# reader-and-latch-client-schematic.net
KiCad netlist of a schematic drawn in EAGLE
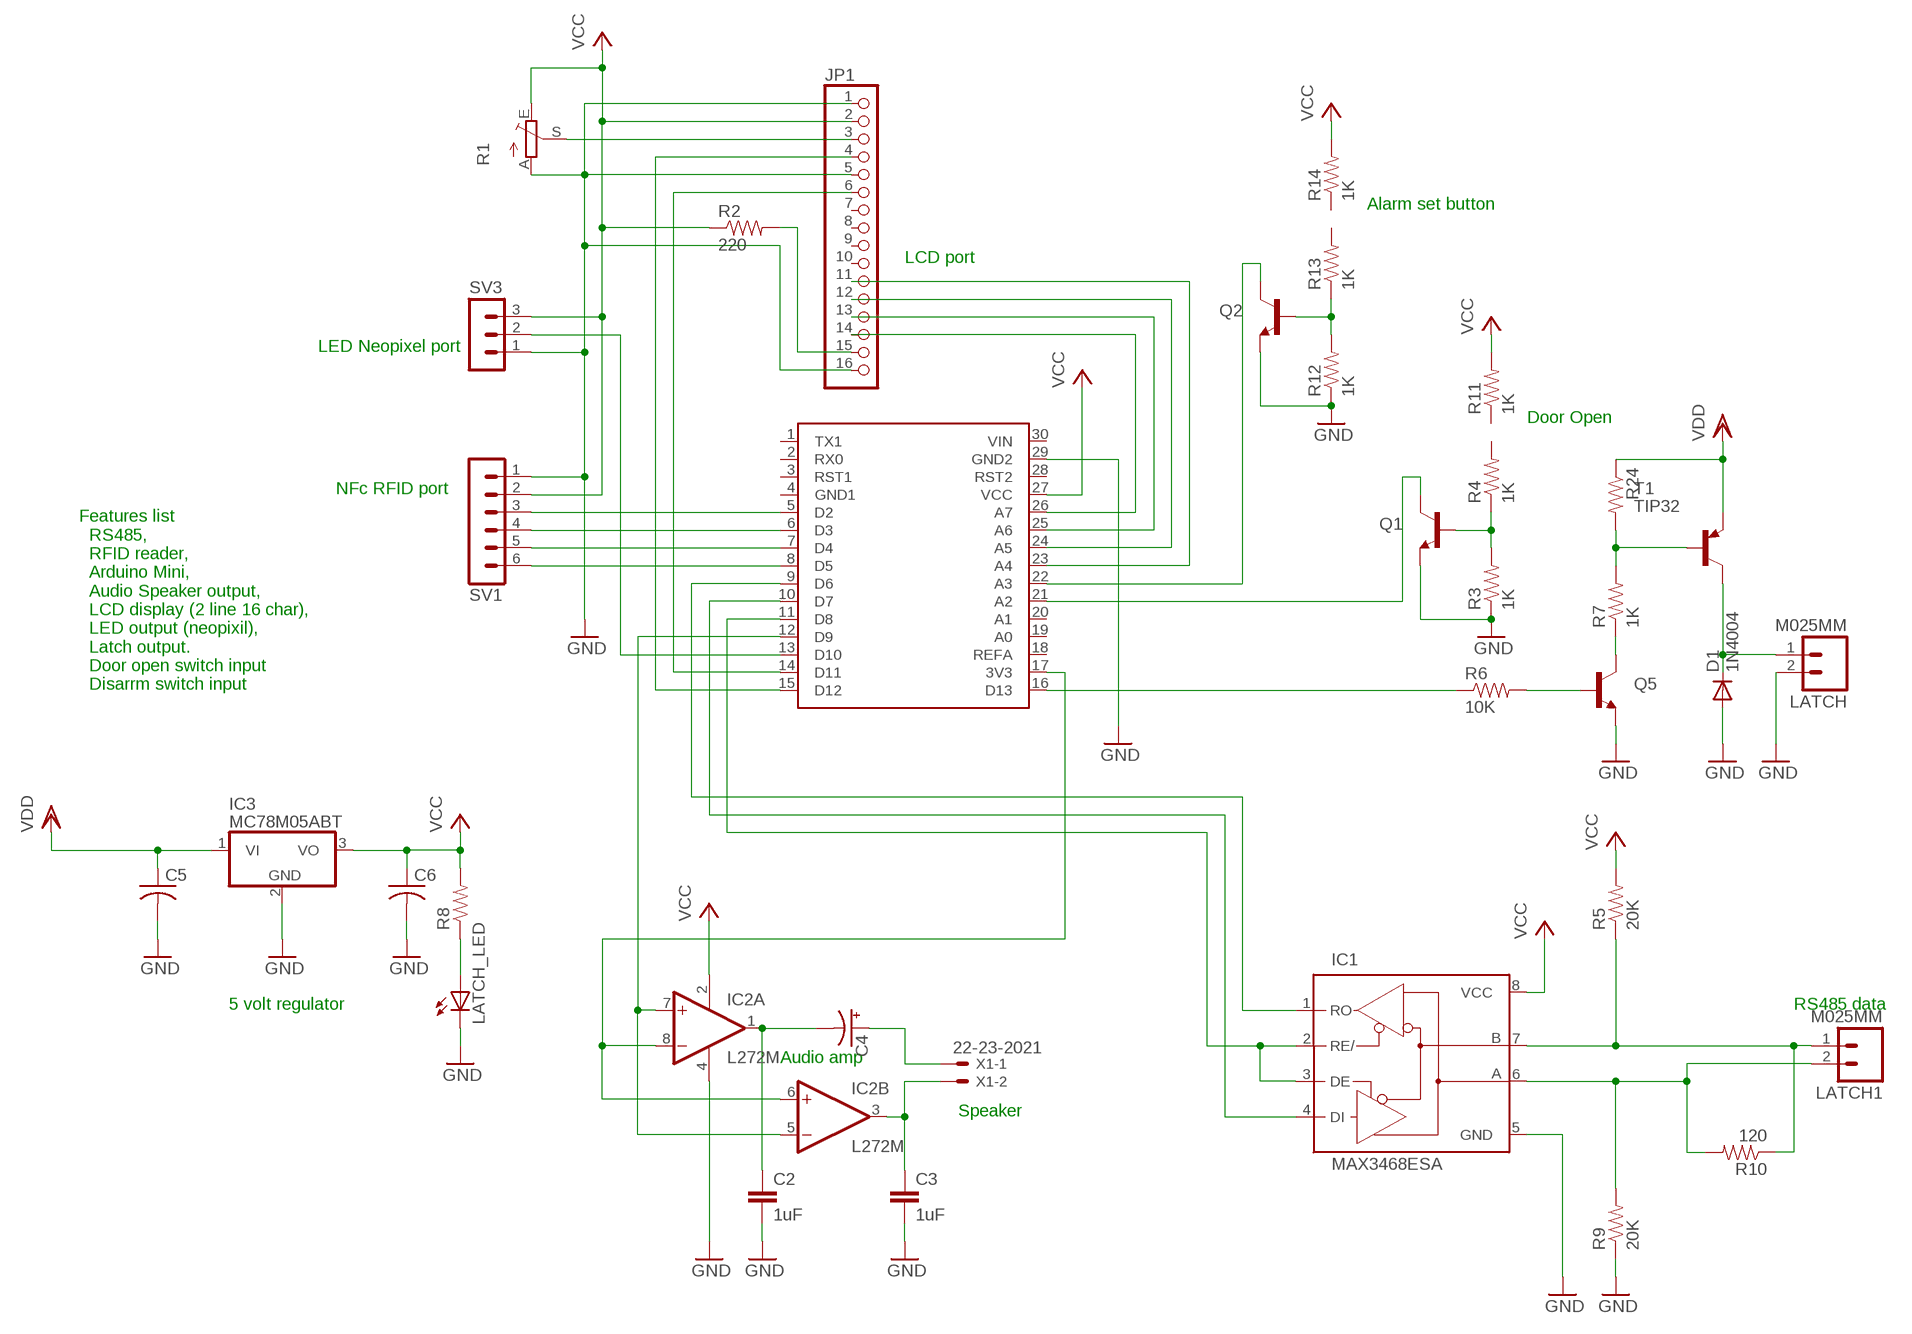
[diagram p0: schematic, sheet 1]

(export (version "E")
  (design (tool "Eeschema 10.0.6"))
  (components
    (comp (ref "C2")
      (value "1uF")
      (footprint "eagle-import:0805")
      (libsource (lib "eagle-import") (part "1UF-25V-10%(0805)"))
    )
    (comp (ref "C3")
      (value "1uF")
      (footprint "eagle-import:0805")
      (libsource (lib "eagle-import") (part "1UF-25V-10%(0805)"))
    )
    (comp (ref "C4")
      (value "CAP_POLPTH1")
      (footprint "eagle-import:CPOL-RADIAL-100UF-25V")
      (libsource (lib "eagle-import") (part "CAP_POLPTH1"))
    )
    (comp (ref "C5")
      (value "C-USC1206")
      (footprint "eagle-import:C1206")
      (libsource (lib "eagle-import") (part "C-USC1206"))
    )
    (comp (ref "C6")
      (value "C-USC1206")
      (footprint "eagle-import:C1206")
      (libsource (lib "eagle-import") (part "C-USC1206"))
    )
    (comp (ref "D1")
      (value "1N4004")
      (footprint "eagle-import:DO41-10")
      (libsource (lib "eagle-import") (part "1N4004"))
    )
    (comp (ref "IC1")
      (value "MAX3468ESA")
      (footprint "eagle-import:SO08")
      (fields (field (name "MPN") "MAX3468ESA+T"))
      (libsource (lib "eagle-import") (part "MAX34SA68E"))
    )
    (comp (ref "IC2")
      (value "L272M")
      (footprint "eagle-import:DIL08")
      (libsource (lib "eagle-import") (part "L272M"))
    )
    (comp (ref "IC3")
      (value "MC78M05ABT")
      (footprint "eagle-import:TO220V")
      (libsource (lib "eagle-import") (part "MC78MT05AB"))
    )
    (comp (ref "JP1")
      (value "PINHD-1X16")
      (footprint "eagle-import:1X16")
      (libsource (lib "eagle-import") (part "PINHD-1X16"))
    )
    (comp (ref "LATCH")
      (value "M025MM")
      (footprint "eagle-import:SCREWTERMINAL-5MM-2")
      (libsource (lib "eagle-import") (part "M025MM"))
    )
    (comp (ref "LATCH1")
      (value "M025MM")
      (footprint "eagle-import:SCREWTERMINAL-5MM-2")
      (libsource (lib "eagle-import") (part "M025MM"))
    )
    (comp (ref "LATCH_LED")
      (value "LED3MM")
      (footprint "eagle-import:LED3MM")
      (libsource (lib "eagle-import") (part "LED3MM"))
    )
    (comp (ref "Q1")
      (value "TRANSISTOR_NPNTO-92-AMMO")
      (footprint "eagle-import:TO-92-AMMO")
      (libsource (lib "eagle-import") (part "TRANSISTOR_NPNTO-92-AMMO"))
    )
    (comp (ref "Q2")
      (value "TRANSISTOR_NPNTO-92-AMMO")
      (footprint "eagle-import:TO-92-AMMO")
      (libsource (lib "eagle-import") (part "TRANSISTOR_NPNTO-92-AMMO"))
    )
    (comp (ref "Q5")
      (value "TRANSISTOR_NPNTO-92-AMMO")
      (footprint "eagle-import:TO-92-AMMO")
      (libsource (lib "eagle-import") (part "TRANSISTOR_NPNTO-92-AMMO"))
    )
    (comp (ref "R1")
      (value "TRIM_EU-CT6")
      (footprint "eagle-import:CT6")
      (libsource (lib "eagle-import") (part "TRIM_EU-CT6"))
    )
    (comp (ref "R2")
      (value "220")
      (footprint "eagle-import:AXIAL-0.3-KIT")
      (libsource (lib "eagle-import") (part "10KOHM1/6W5%(PTH)KIT"))
    )
    (comp (ref "R3")
      (value "1K")
      (footprint "eagle-import:AXIAL-0.3-KIT")
      (libsource (lib "eagle-import") (part "10KOHM1/6W5%(PTH)KIT"))
    )
    (comp (ref "R4")
      (value "1K")
      (footprint "eagle-import:AXIAL-0.3-KIT")
      (libsource (lib "eagle-import") (part "10KOHM1/6W5%(PTH)KIT"))
    )
    (comp (ref "R5")
      (value "20K")
      (footprint "eagle-import:AXIAL-0.3-KIT")
      (libsource (lib "eagle-import") (part "10KOHM1/6W5%(PTH)KIT"))
    )
    (comp (ref "R6")
      (value "10K")
      (footprint "eagle-import:AXIAL-0.3-KIT")
      (libsource (lib "eagle-import") (part "10KOHM1/6W5%(PTH)KIT"))
    )
    (comp (ref "R7")
      (value "1K")
      (footprint "eagle-import:AXIAL-0.3-KIT")
      (libsource (lib "eagle-import") (part "10KOHM1/6W5%(PTH)KIT"))
    )
    (comp (ref "R8")
      (value "10KOHM1/6W5%(PTH)KIT")
      (footprint "eagle-import:AXIAL-0.3-KIT")
      (libsource (lib "eagle-import") (part "10KOHM1/6W5%(PTH)KIT"))
    )
    (comp (ref "R9")
      (value "20K")
      (footprint "eagle-import:AXIAL-0.3-KIT")
      (libsource (lib "eagle-import") (part "10KOHM1/6W5%(PTH)KIT"))
    )
    (comp (ref "R10")
      (value "120")
      (footprint "eagle-import:AXIAL-0.3-KIT")
      (libsource (lib "eagle-import") (part "10KOHM1/6W5%(PTH)KIT"))
    )
    (comp (ref "R11")
      (value "1K")
      (footprint "eagle-import:AXIAL-0.3-KIT")
      (libsource (lib "eagle-import") (part "10KOHM1/6W5%(PTH)KIT"))
    )
    (comp (ref "R12")
      (value "1K")
      (footprint "eagle-import:AXIAL-0.3-KIT")
      (libsource (lib "eagle-import") (part "10KOHM1/6W5%(PTH)KIT"))
    )
    (comp (ref "R13")
      (value "1K")
      (footprint "eagle-import:AXIAL-0.3-KIT")
      (libsource (lib "eagle-import") (part "10KOHM1/6W5%(PTH)KIT"))
    )
    (comp (ref "R14")
      (value "1K")
      (footprint "eagle-import:AXIAL-0.3-KIT")
      (libsource (lib "eagle-import") (part "10KOHM1/6W5%(PTH)KIT"))
    )
    (comp (ref "R24")
      (value "10KOHM1/6W5%(PTH)KIT")
      (footprint "eagle-import:AXIAL-0.3-KIT")
      (libsource (lib "eagle-import") (part "10KOHM1/6W5%(PTH)KIT"))
    )
    (comp (ref "SV1")
      (value "MA06-1")
      (footprint "eagle-import:MA06-1")
      (libsource (lib "eagle-import") (part "MA06-1"))
    )
    (comp (ref "SV3")
      (value "MA03-1")
      (footprint "eagle-import:MA03-1")
      (libsource (lib "eagle-import") (part "MA03-1"))
    )
    (comp (ref "T1")
      (value "TIP32")
      (footprint "eagle-import:TO220")
      (libsource (lib "eagle-import") (part "TIP32"))
    )
    (comp (ref "U$1")
      (value "ARDUINO-NANO")
      (footprint "eagle-import:ARDUINO-NANO")
      (libsource (lib "eagle-import") (part "ARDUINO-NANO"))
    )
    (comp (ref "X1")
      (value "22-23-2021")
      (footprint "eagle-import:22-23-2021")
      (fields (field (name "MF") "MOLEX"))
      (libsource (lib "eagle-import") (part "22-23-2021"))
    )
  )
  (nets
    (net (code "1") (name "GND") (class "Default")
      (node (ref "C2") (pin "2") (pinfunction "2_2") (pintype "passive"))
      (node (ref "C3") (pin "2") (pinfunction "2_2") (pintype "passive"))
      (node (ref "C5") (pin "2") (pinfunction "2_2") (pintype "passive"))
      (node (ref "C6") (pin "2") (pinfunction "2_2") (pintype "passive"))
      (node (ref "D1") (pin "A") (pinfunction "A_A") (pintype "passive"))
      (node (ref "IC1") (pin "5") (pinfunction "GND_5") (pintype "power_in"))
      (node (ref "IC2") (pin "4") (pinfunction "GND_4") (pintype "power_in"))
      (node (ref "IC3") (pin "2") (pinfunction "GND_2") (pintype "passive"))
      (node (ref "JP1") (pin "1") (pinfunction "1_1") (pintype "passive"))
      (node (ref "JP1") (pin "16") (pinfunction "16_16") (pintype "passive"))
      (node (ref "JP1") (pin "5") (pinfunction "5_5") (pintype "passive"))
      (node (ref "LATCH") (pin "2") (pinfunction "2_2") (pintype "passive"))
      (node (ref "LATCH_LED") (pin "K") (pinfunction "C_K") (pintype "passive"))
      (node (ref "Q1") (pin "1") (pinfunction "E_1") (pintype "passive"))
      (node (ref "Q2") (pin "1") (pinfunction "E_1") (pintype "passive"))
      (node (ref "Q5") (pin "1") (pinfunction "E_1") (pintype "passive"))
      (node (ref "R1") (pin "A") (pinfunction "A_A") (pintype "passive"))
      (node (ref "R12") (pin "P$1") (pinfunction "1_P$1") (pintype "passive"))
      (node (ref "R3") (pin "P$1") (pinfunction "1_P$1") (pintype "passive"))
      (node (ref "R9") (pin "P$1") (pinfunction "1_P$1") (pintype "passive"))
      (node (ref "SV1") (pin "1") (pinfunction "1_1") (pintype "passive"))
      (node (ref "SV3") (pin "1") (pinfunction "1_1") (pintype "passive"))
      (node (ref "U$1") (pin "29") (pinfunction "GND2_29") (pintype "bidirectional"))
    )
    (net (code "2") (name "Net-(C4-+)") (class "Default")
      (node (ref "C4") (pin "1") (pinfunction "+_1") (pintype "passive"))
      (node (ref "X1") (pin "1") (pinfunction "S_1") (pintype "passive"))
    )
    (net (code "3") (name "Net-(C4--)") (class "Default")
      (node (ref "C2") (pin "1") (pinfunction "1_1") (pintype "passive"))
      (node (ref "C4") (pin "2") (pinfunction "-_2") (pintype "passive"))
      (node (ref "IC2") (pin "1") (pinfunction "OUT_1") (pintype "output"))
    )
    (net (code "4") (name "Net-(IC1-A)") (class "Default")
      (node (ref "IC1") (pin "6") (pinfunction "A_6") (pintype "passive"))
      (node (ref "LATCH1") (pin "2") (pinfunction "2_2") (pintype "passive"))
      (node (ref "R10") (pin "P$2") (pinfunction "2_P$2") (pintype "passive"))
      (node (ref "R9") (pin "P$2") (pinfunction "2_P$2") (pintype "passive"))
    )
    (net (code "5") (name "Net-(IC1-B)") (class "Default")
      (node (ref "IC1") (pin "7") (pinfunction "B_7") (pintype "passive"))
      (node (ref "LATCH1") (pin "1") (pinfunction "1_1") (pintype "passive"))
      (node (ref "R10") (pin "P$1") (pinfunction "1_P$1") (pintype "passive"))
      (node (ref "R5") (pin "P$1") (pinfunction "1_P$1") (pintype "passive"))
    )
    (net (code "6") (name "Net-(IC1-DE)") (class "Default")
      (node (ref "IC1") (pin "2") (pinfunction "RE/_2") (pintype "input"))
      (node (ref "IC1") (pin "3") (pinfunction "DE_3") (pintype "input"))
      (node (ref "U$1") (pin "11") (pinfunction "D8_11") (pintype "bidirectional"))
    )
    (net (code "7") (name "Net-(IC1-DI)") (class "Default")
      (node (ref "IC1") (pin "4") (pinfunction "DI_4") (pintype "input"))
      (node (ref "U$1") (pin "10") (pinfunction "D7_10") (pintype "bidirectional"))
    )
    (net (code "8") (name "Net-(IC1-RO)") (class "Default")
      (node (ref "IC1") (pin "1") (pinfunction "RO_1") (pintype "output"))
      (node (ref "U$1") (pin "9") (pinfunction "D6_9") (pintype "bidirectional"))
    )
    (net (code "9") (name "Net-(IC2A-+IN)") (class "Default")
      (node (ref "IC2") (pin "5") (pinfunction "-IN_5") (pintype "input"))
      (node (ref "IC2") (pin "7") (pinfunction "+IN_7") (pintype "input"))
      (node (ref "U$1") (pin "12") (pinfunction "D9_12") (pintype "bidirectional"))
    )
    (net (code "10") (name "Net-(IC2A--IN)") (class "Default")
      (node (ref "IC2") (pin "6") (pinfunction "+IN_6") (pintype "input"))
      (node (ref "IC2") (pin "8") (pinfunction "-IN_8") (pintype "input"))
      (node (ref "U$1") (pin "17") (pinfunction "3V3_17") (pintype "bidirectional"))
    )
    (net (code "11") (name "Net-(IC2B-OUT)") (class "Default")
      (node (ref "C3") (pin "1") (pinfunction "1_1") (pintype "passive"))
      (node (ref "IC2") (pin "3") (pinfunction "OUT_3") (pintype "output"))
      (node (ref "X1") (pin "2") (pinfunction "S_2") (pintype "passive"))
    )
    (net (code "12") (name "Net-(JP1-Pad3)") (class "Default")
      (node (ref "JP1") (pin "3") (pinfunction "3_3") (pintype "passive"))
      (node (ref "R1") (pin "S") (pinfunction "S_S") (pintype "passive"))
    )
    (net (code "13") (name "Net-(Q1-B)") (class "Default")
      (node (ref "Q1") (pin "2") (pinfunction "B_2") (pintype "passive"))
      (node (ref "R3") (pin "P$2") (pinfunction "2_P$2") (pintype "passive"))
      (node (ref "R4") (pin "P$1") (pinfunction "1_P$1") (pintype "passive"))
    )
    (net (code "14") (name "Net-(Q1-C)") (class "Default")
      (node (ref "Q1") (pin "3") (pinfunction "C_3") (pintype "passive"))
      (node (ref "U$1") (pin "21") (pinfunction "A2_21") (pintype "bidirectional"))
    )
    (net (code "15") (name "Net-(Q2-B)") (class "Default")
      (node (ref "Q2") (pin "2") (pinfunction "B_2") (pintype "passive"))
      (node (ref "R12") (pin "P$2") (pinfunction "2_P$2") (pintype "passive"))
      (node (ref "R13") (pin "P$1") (pinfunction "1_P$1") (pintype "passive"))
    )
    (net (code "16") (name "Net-(Q2-C)") (class "Default")
      (node (ref "Q2") (pin "3") (pinfunction "C_3") (pintype "passive"))
      (node (ref "U$1") (pin "22") (pinfunction "A3_22") (pintype "bidirectional"))
    )
    (net (code "17") (name "Net-(Q5-B)") (class "Default")
      (node (ref "Q5") (pin "2") (pinfunction "B_2") (pintype "passive"))
      (node (ref "R6") (pin "P$2") (pinfunction "2_P$2") (pintype "passive"))
    )
    (net (code "18") (name "Net-(Q5-C)") (class "Default")
      (node (ref "Q5") (pin "3") (pinfunction "C_3") (pintype "passive"))
      (node (ref "R7") (pin "P$1") (pinfunction "1_P$1") (pintype "passive"))
    )
    (net (code "19") (name "Net-(R2-2)") (class "Default")
      (node (ref "JP1") (pin "15") (pinfunction "15_15") (pintype "passive"))
      (node (ref "R2") (pin "P$2") (pinfunction "2_P$2") (pintype "passive"))
    )
    (net (code "20") (name "Net-(R6-1)") (class "Default")
      (node (ref "R6") (pin "P$1") (pinfunction "1_P$1") (pintype "passive"))
      (node (ref "U$1") (pin "16") (pinfunction "D13_16") (pintype "bidirectional"))
    )
    (net (code "21") (name "Net-(R8-1)") (class "Default")
      (node (ref "LATCH_LED") (pin "A") (pinfunction "A_A") (pintype "passive"))
      (node (ref "R8") (pin "P$1") (pinfunction "1_P$1") (pintype "passive"))
    )
    (net (code "22") (name "Net-(R24-2)") (class "Default")
      (node (ref "R24") (pin "P$2") (pinfunction "2_P$2") (pintype "passive"))
      (node (ref "R7") (pin "P$2") (pinfunction "2_P$2") (pintype "passive"))
      (node (ref "T1") (pin "1") (pinfunction "B_1") (pintype "passive"))
    )
    (net (code "23") (name "Net-(T1-C)") (class "Default")
      (node (ref "D1") (pin "C") (pinfunction "C_C") (pintype "passive"))
      (node (ref "LATCH") (pin "1") (pinfunction "1_1") (pintype "passive"))
      (node (ref "T1") (pin "2") (pinfunction "C_2") (pintype "passive"))
    )
    (net (code "24") (name "Net-(U$1-A4)") (class "Default")
      (node (ref "JP1") (pin "11") (pinfunction "11_11") (pintype "passive"))
      (node (ref "U$1") (pin "23") (pinfunction "A4_23") (pintype "bidirectional"))
    )
    (net (code "25") (name "Net-(U$1-A5)") (class "Default")
      (node (ref "JP1") (pin "12") (pinfunction "12_12") (pintype "passive"))
      (node (ref "U$1") (pin "24") (pinfunction "A5_24") (pintype "bidirectional"))
    )
    (net (code "26") (name "Net-(U$1-A6)") (class "Default")
      (node (ref "JP1") (pin "13") (pinfunction "13_13") (pintype "passive"))
      (node (ref "U$1") (pin "25") (pinfunction "A6_25") (pintype "bidirectional"))
    )
    (net (code "27") (name "Net-(U$1-A7)") (class "Default")
      (node (ref "JP1") (pin "14") (pinfunction "14_14") (pintype "passive"))
      (node (ref "U$1") (pin "26") (pinfunction "A7_26") (pintype "bidirectional"))
    )
    (net (code "28") (name "Net-(U$1-D2)") (class "Default")
      (node (ref "SV1") (pin "3") (pinfunction "3_3") (pintype "passive"))
      (node (ref "U$1") (pin "5") (pinfunction "D2_5") (pintype "bidirectional"))
    )
    (net (code "29") (name "Net-(U$1-D3)") (class "Default")
      (node (ref "SV1") (pin "4") (pinfunction "4_4") (pintype "passive"))
      (node (ref "U$1") (pin "6") (pinfunction "D3_6") (pintype "bidirectional"))
    )
    (net (code "30") (name "Net-(U$1-D4)") (class "Default")
      (node (ref "SV1") (pin "5") (pinfunction "5_5") (pintype "passive"))
      (node (ref "U$1") (pin "7") (pinfunction "D4_7") (pintype "bidirectional"))
    )
    (net (code "31") (name "Net-(U$1-D5)") (class "Default")
      (node (ref "SV1") (pin "6") (pinfunction "6_6") (pintype "passive"))
      (node (ref "U$1") (pin "8") (pinfunction "D5_8") (pintype "bidirectional"))
    )
    (net (code "32") (name "Net-(U$1-D10)") (class "Default")
      (node (ref "SV3") (pin "2") (pinfunction "2_2") (pintype "passive"))
      (node (ref "U$1") (pin "13") (pinfunction "D10_13") (pintype "bidirectional"))
    )
    (net (code "33") (name "Net-(U$1-D11)") (class "Default")
      (node (ref "JP1") (pin "6") (pinfunction "6_6") (pintype "passive"))
      (node (ref "U$1") (pin "14") (pinfunction "D11_14") (pintype "bidirectional"))
    )
    (net (code "34") (name "Net-(U$1-D12)") (class "Default")
      (node (ref "JP1") (pin "4") (pinfunction "4_4") (pintype "passive"))
      (node (ref "U$1") (pin "15") (pinfunction "D12_15") (pintype "bidirectional"))
    )
    (net (code "35") (name "VCC") (class "Default")
      (node (ref "C6") (pin "1") (pinfunction "1_1") (pintype "passive"))
      (node (ref "IC1") (pin "8") (pinfunction "VCC_8") (pintype "power_in"))
      (node (ref "IC2") (pin "2") (pinfunction "V+_2") (pintype "power_in"))
      (node (ref "IC3") (pin "3") (pinfunction "VO_3") (pintype "passive"))
      (node (ref "JP1") (pin "2") (pinfunction "2_2") (pintype "passive"))
      (node (ref "R1") (pin "E") (pinfunction "E_E") (pintype "passive"))
      (node (ref "R11") (pin "P$2") (pinfunction "2_P$2") (pintype "passive"))
      (node (ref "R14") (pin "P$2") (pinfunction "2_P$2") (pintype "passive"))
      (node (ref "R2") (pin "P$1") (pinfunction "1_P$1") (pintype "passive"))
      (node (ref "R5") (pin "P$2") (pinfunction "2_P$2") (pintype "passive"))
      (node (ref "R8") (pin "P$2") (pinfunction "2_P$2") (pintype "passive"))
      (node (ref "SV1") (pin "2") (pinfunction "2_2") (pintype "passive"))
      (node (ref "SV3") (pin "3") (pinfunction "3_3") (pintype "passive"))
      (node (ref "U$1") (pin "27") (pinfunction "VCC_27") (pintype "bidirectional"))
    )
    (net (code "36") (name "VDD") (class "Default")
      (node (ref "C5") (pin "1") (pinfunction "1_1") (pintype "passive"))
      (node (ref "IC3") (pin "1") (pinfunction "VI_1") (pintype "input"))
      (node (ref "R24") (pin "P$1") (pinfunction "1_P$1") (pintype "passive"))
      (node (ref "T1") (pin "3") (pinfunction "E_3") (pintype "passive"))
    )
    (net (code "37") (name "unconnected-(JP1-Pad7)") (class "Default")
      (node (ref "JP1") (pin "7") (pinfunction "7_7") (pintype "passive"))
    )
    (net (code "38") (name "unconnected-(JP1-Pad8)") (class "Default")
      (node (ref "JP1") (pin "8") (pinfunction "8_8") (pintype "passive"))
    )
    (net (code "39") (name "unconnected-(JP1-Pad9)") (class "Default")
      (node (ref "JP1") (pin "9") (pinfunction "9_9") (pintype "passive"))
    )
    (net (code "40") (name "unconnected-(JP1-Pad10)") (class "Default")
      (node (ref "JP1") (pin "10") (pinfunction "10_10") (pintype "passive"))
    )
    (net (code "41") (name "unconnected-(R4-2-PadP$2)") (class "Default")
      (node (ref "R4") (pin "P$2") (pinfunction "2_P$2") (pintype "passive"))
    )
    (net (code "42") (name "unconnected-(R11-1-PadP$1)") (class "Default")
      (node (ref "R11") (pin "P$1") (pinfunction "1_P$1") (pintype "passive"))
    )
    (net (code "43") (name "unconnected-(R13-2-PadP$2)") (class "Default")
      (node (ref "R13") (pin "P$2") (pinfunction "2_P$2") (pintype "passive"))
    )
    (net (code "44") (name "unconnected-(R14-1-PadP$1)") (class "Default")
      (node (ref "R14") (pin "P$1") (pinfunction "1_P$1") (pintype "passive"))
    )
    (net (code "45") (name "unconnected-(U$1-A0-Pad19)") (class "Default")
      (node (ref "U$1") (pin "19") (pinfunction "A0_19") (pintype "bidirectional"))
    )
    (net (code "46") (name "unconnected-(U$1-A1-Pad20)") (class "Default")
      (node (ref "U$1") (pin "20") (pinfunction "A1_20") (pintype "bidirectional"))
    )
    (net (code "47") (name "unconnected-(U$1-GND1-Pad4)") (class "Default")
      (node (ref "U$1") (pin "4") (pinfunction "GND1_4") (pintype "bidirectional"))
    )
    (net (code "48") (name "unconnected-(U$1-REFA-Pad18)") (class "Default")
      (node (ref "U$1") (pin "18") (pinfunction "REFA_18") (pintype "bidirectional"))
    )
    (net (code "49") (name "unconnected-(U$1-RST1-Pad3)") (class "Default")
      (node (ref "U$1") (pin "3") (pinfunction "RST1_3") (pintype "bidirectional"))
    )
    (net (code "50") (name "unconnected-(U$1-RST2-Pad28)") (class "Default")
      (node (ref "U$1") (pin "28") (pinfunction "RST2_28") (pintype "bidirectional"))
    )
    (net (code "51") (name "unconnected-(U$1-RX0-Pad2)") (class "Default")
      (node (ref "U$1") (pin "2") (pinfunction "RX0_2") (pintype "bidirectional"))
    )
    (net (code "52") (name "unconnected-(U$1-TX1-Pad1)") (class "Default")
      (node (ref "U$1") (pin "1") (pinfunction "TX1_1") (pintype "bidirectional"))
    )
    (net (code "53") (name "unconnected-(U$1-VIN-Pad30)") (class "Default")
      (node (ref "U$1") (pin "30") (pinfunction "VIN_30") (pintype "bidirectional"))
    )
  )
)
